# Microcontroller.net
KiCad netlist of a schematic drawn in Altium Designer
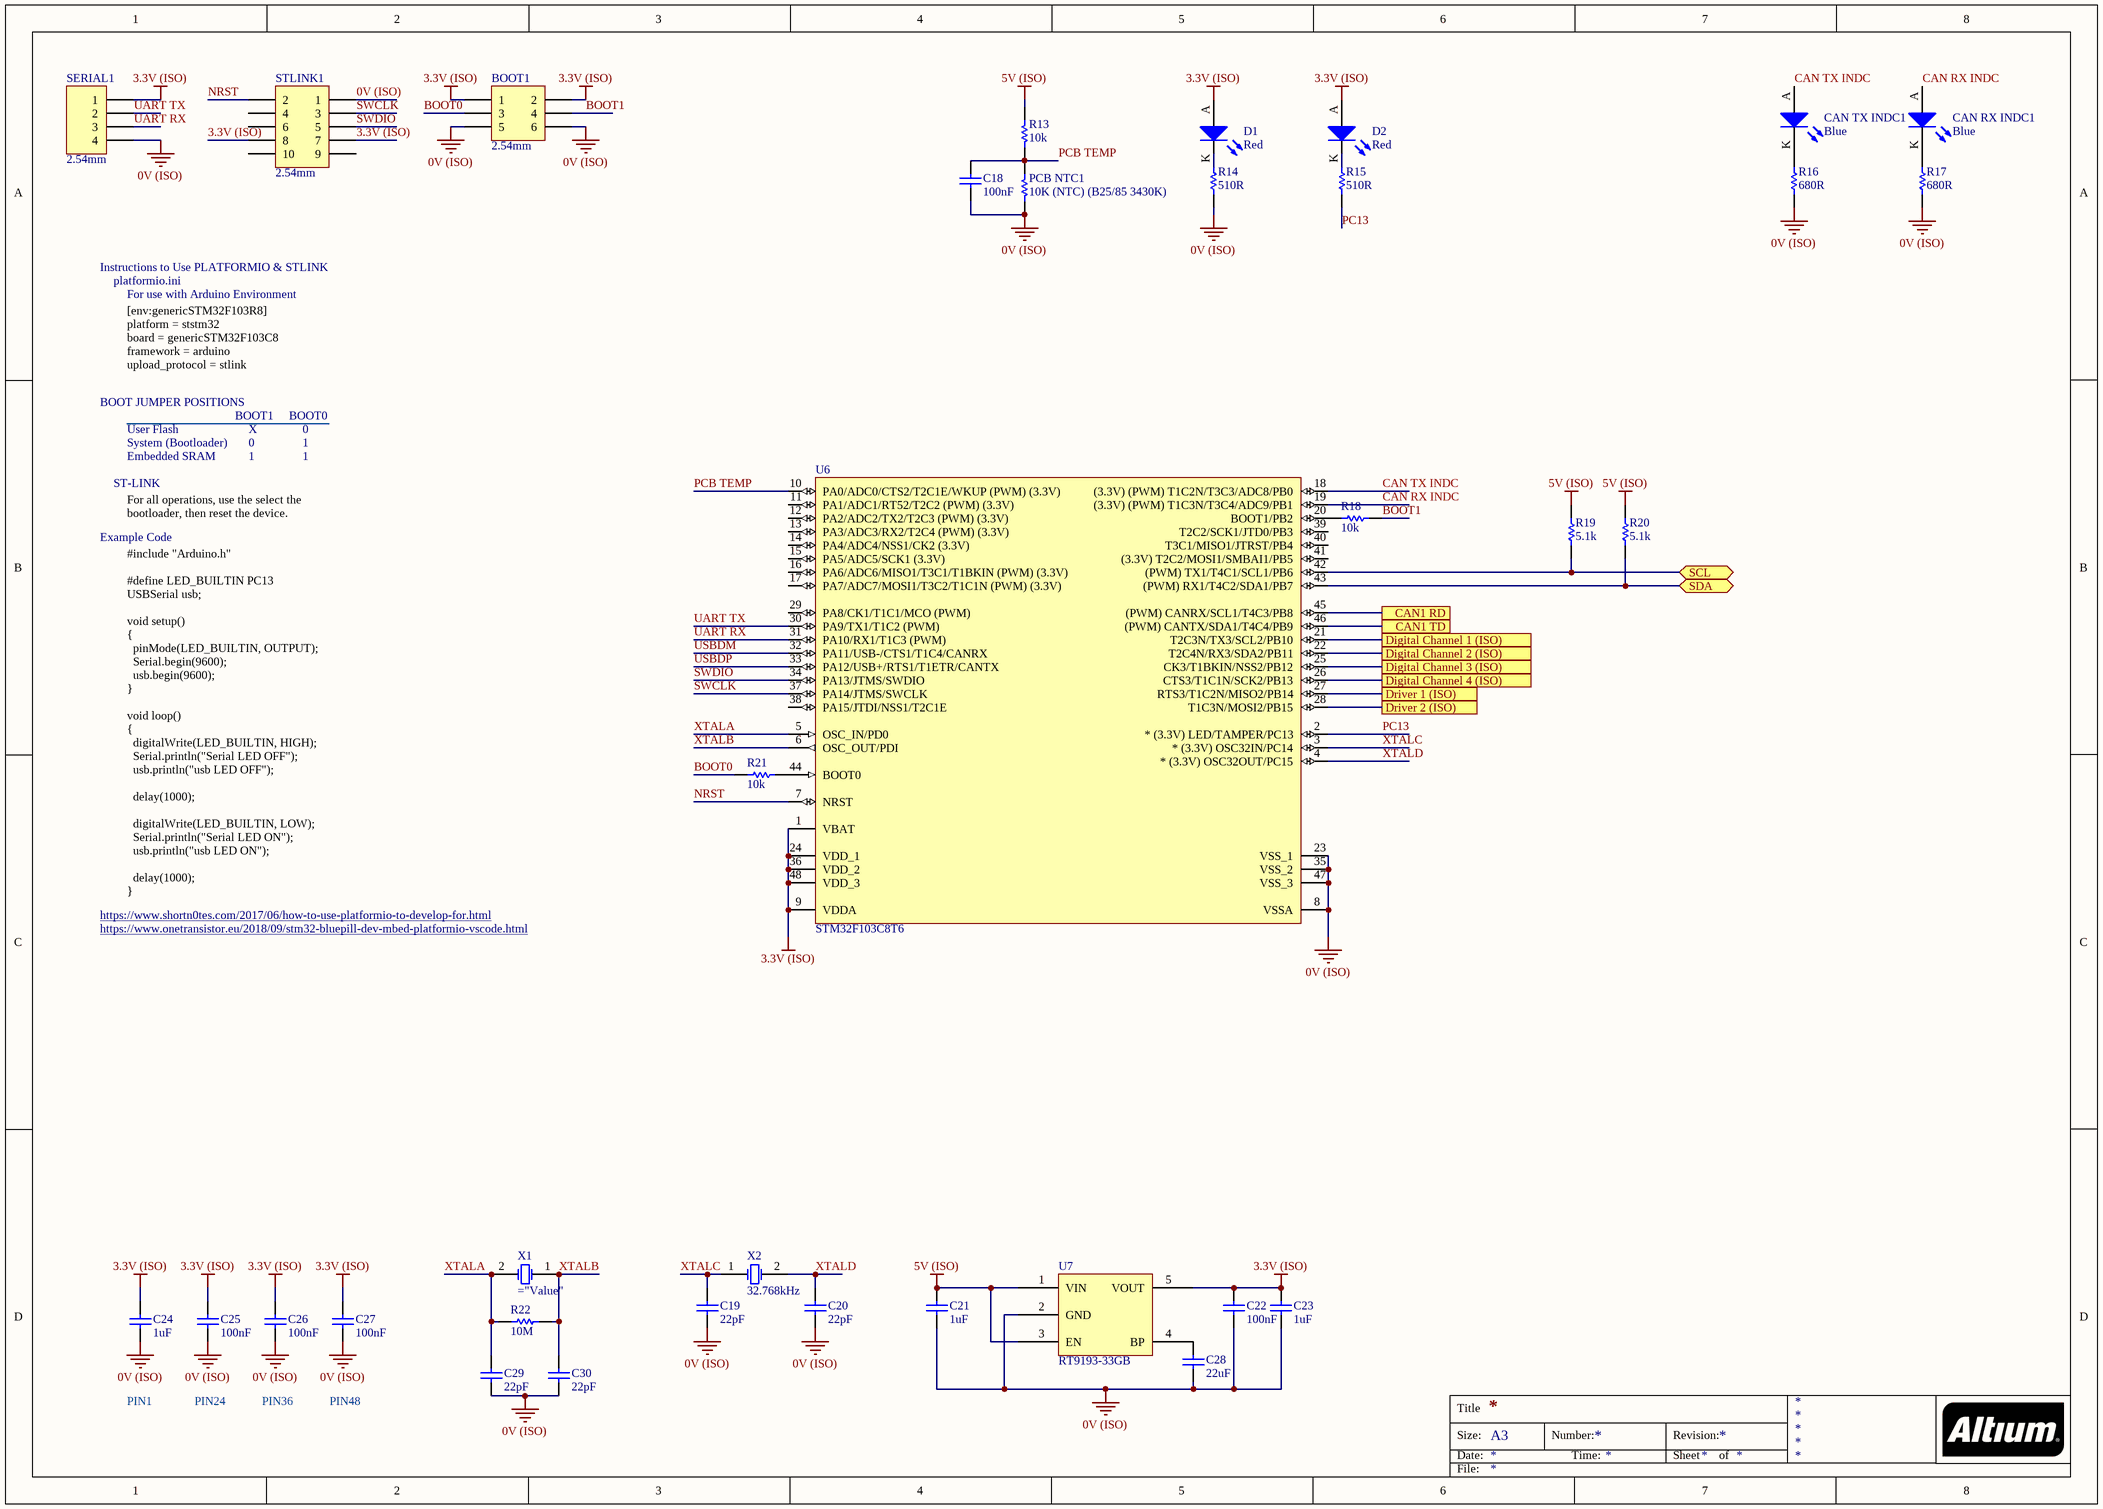
[diagram p0: Microcontroller.SchDoc]

(export (version "E")
  (design (tool "Eeschema 10.0.6"))
  (components
    (comp (ref "BOOT1")
      (value "2.54mm")
      (footprint "TH 2.54mm Header 2x3")
      (fields (field (name "PART NUMBER") "TH 2.54mm Header 2x3") (field (name "CONTACT") "NA"))
      (libsource (lib "ts_20-standard-connectors") (part "Header 2x3"))
    )
    (comp (ref "C18")
      (value "100nF")
      (footprint "0805")
      (fields
        (field (name "PART NUMBER") "GCM21BR71E104KA37L")
        (field (name "TOLERANCE") "10%")
        (field (name "MANUFACTURER") "muRata")
      )
      (libsource (lib "ts_20-standard-library") (part "Capacitor"))
    )
    (comp (ref "C19")
      (value "22pF")
      (footprint "0805")
      (fields
        (field (name "PART NUMBER") "GCM21B5C1H220JA37L")
        (field (name "TOLERANCE") "5%")
        (field (name "MANUFACTURER") "muRata")
      )
      (libsource (lib "ts_20-standard-library") (part "Capacitor"))
    )
    (comp (ref "C20")
      (value "22pF")
      (footprint "0805")
      (fields
        (field (name "PART NUMBER") "GCM21B5C1H220JA37L")
        (field (name "TOLERANCE") "5%")
        (field (name "MANUFACTURER") "muRata")
      )
      (libsource (lib "ts_20-standard-library") (part "Capacitor"))
    )
    (comp (ref "C21")
      (value "1uF")
      (footprint "0805")
      (fields
        (field (name "PART NUMBER") "AC0805KKX7R8BB105")
        (field (name "TOLERANCE") "10%")
        (field (name "MANUFACTURER") "YAGEO")
      )
      (libsource (lib "ts_20-standard-library") (part "Capacitor"))
    )
    (comp (ref "C22")
      (value "100nF")
      (footprint "0805")
      (fields
        (field (name "PART NUMBER") "GCM21BR71E104KA37L")
        (field (name "TOLERANCE") "10%")
        (field (name "MANUFACTURER") "muRata")
      )
      (libsource (lib "ts_20-standard-library") (part "Capacitor"))
    )
    (comp (ref "C23")
      (value "1uF")
      (footprint "0805")
      (fields
        (field (name "PART NUMBER") "AC0805KKX7R8BB105")
        (field (name "TOLERANCE") "10%")
        (field (name "MANUFACTURER") "YAGEO")
      )
      (libsource (lib "ts_20-standard-library") (part "Capacitor"))
    )
    (comp (ref "C24")
      (value "1uF")
      (footprint "0805")
      (fields
        (field (name "PART NUMBER") "AC0805KKX7R8BB105")
        (field (name "TOLERANCE") "10%")
        (field (name "MANUFACTURER") "YAGEO")
      )
      (libsource (lib "ts_20-standard-library") (part "Capacitor"))
    )
    (comp (ref "C25")
      (value "100nF")
      (footprint "0805")
      (fields
        (field (name "PART NUMBER") "GCM21BR71E104KA37L")
        (field (name "TOLERANCE") "10%")
        (field (name "MANUFACTURER") "muRata")
      )
      (libsource (lib "ts_20-standard-library") (part "Capacitor"))
    )
    (comp (ref "C26")
      (value "100nF")
      (footprint "0805")
      (fields
        (field (name "PART NUMBER") "GCM21BR71E104KA37L")
        (field (name "TOLERANCE") "10%")
        (field (name "MANUFACTURER") "muRata")
      )
      (libsource (lib "ts_20-standard-library") (part "Capacitor"))
    )
    (comp (ref "C27")
      (value "100nF")
      (footprint "0805")
      (fields
        (field (name "PART NUMBER") "GCM21BR71E104KA37L")
        (field (name "TOLERANCE") "10%")
        (field (name "MANUFACTURER") "muRata")
      )
      (libsource (lib "ts_20-standard-library") (part "Capacitor"))
    )
    (comp (ref "C28")
      (value "22uF")
      (footprint "0805")
      (fields
        (field (name "PART NUMBER") "GRM21BR61A226ME51L")
        (field (name "TOLERANCE") "20%")
        (field (name "MANUFACTURER") "muRata")
      )
      (libsource (lib "ts_20-standard-library") (part "Capacitor"))
    )
    (comp (ref "C29")
      (value "22pF")
      (footprint "0805")
      (fields
        (field (name "PART NUMBER") "GCM21B5C1H220JA37L")
        (field (name "TOLERANCE") "5%")
        (field (name "MANUFACTURER") "muRata")
      )
      (libsource (lib "ts_20-standard-library") (part "Capacitor"))
    )
    (comp (ref "C30")
      (value "22pF")
      (footprint "0805")
      (fields
        (field (name "PART NUMBER") "GCM21B5C1H220JA37L")
        (field (name "TOLERANCE") "5%")
        (field (name "MANUFACTURER") "muRata")
      )
      (libsource (lib "ts_20-standard-library") (part "Capacitor"))
    )
    (comp (ref "CAN RX INDC1")
      (value "Blue")
      (footprint "0805 LED")
      (description "LED BLUE CLEAR 2012 SMD")
      (fields
        (field (name "PART NUMBER") "SML-MN2BCTT86C")
        (field (name "MANUFACTURER") "ROHM Semiconductor")
      )
      (libsource (lib "ts_20-standard-library") (part "LED"))
    )
    (comp (ref "CAN TX INDC1")
      (value "Blue")
      (footprint "0805 LED")
      (description "LED BLUE CLEAR 2012 SMD")
      (fields
        (field (name "PART NUMBER") "SML-MN2BCTT86C")
        (field (name "MANUFACTURER") "ROHM Semiconductor")
      )
      (libsource (lib "ts_20-standard-library") (part "LED"))
    )
    (comp (ref "D1")
      (value "Red")
      (footprint "0805 LED")
      (description "Red LED Indication - Discrete 1.75V 0805 (2012 Metric)")
      (fields (field (name "MANUFACTURER") "ROHM Semiconductor") (field (name "PART NUMBER") "SML-210LTT86"))
      (libsource (lib "ts_20-standard-library") (part "LED"))
    )
    (comp (ref "D2")
      (value "Red")
      (footprint "0805 LED")
      (description "Red LED Indication - Discrete 1.75V 0805 (2012 Metric)")
      (fields (field (name "MANUFACTURER") "ROHM Semiconductor") (field (name "PART NUMBER") "SML-210LTT86"))
      (libsource (lib "ts_20-standard-library") (part "LED"))
    )
    (comp (ref "PCB NTC1")
      (value "10K (NTC) (B25/85 3430K)")
      (footprint "0805")
      (fields
        (field (name "PART NUMBER") "NTCS0805E3103FLT")
        (field (name "MANUFACTURER") "Vishay Beyschlag")
        (field (name "TOLERANCE") "0.01")
      )
      (libsource (lib "ts_20-standard-library") (part "Resistor"))
    )
    (comp (ref "R13")
      (value "10k")
      (footprint "0805")
      (fields
        (field (name "PART NUMBER") "RC0805FR0710KL")
        (field (name "MANUFACTURER") "YAGEO")
        (field (name "TOLERANCE") "0.01")
      )
      (libsource (lib "ts_20-standard-library") (part "Resistor"))
    )
    (comp (ref "R14")
      (value "510R")
      (footprint "0805")
      (fields
        (field (name "MANUFACTURER") "YAGEO")
        (field (name "PART NUMBER") "RC0805FR07510RL")
        (field (name "TOLERANCE") "0.01")
      )
      (libsource (lib "ts_20-standard-library") (part "Resistor"))
    )
    (comp (ref "R15")
      (value "510R")
      (footprint "0805")
      (fields
        (field (name "MANUFACTURER") "YAGEO")
        (field (name "PART NUMBER") "RC0805FR07510RL")
        (field (name "TOLERANCE") "0.01")
      )
      (libsource (lib "ts_20-standard-library") (part "Resistor"))
    )
    (comp (ref "R16")
      (value "680R")
      (footprint "0805")
      (fields
        (field (name "PART NUMBER") "RC0805FR07680RL")
        (field (name "MANUFACTURER") "YAGEO")
        (field (name "TOLERANCE") "0.01")
      )
      (libsource (lib "ts_20-standard-library") (part "Resistor"))
    )
    (comp (ref "R17")
      (value "680R")
      (footprint "0805")
      (fields
        (field (name "PART NUMBER") "RC0805FR07680RL")
        (field (name "MANUFACTURER") "YAGEO")
        (field (name "TOLERANCE") "0.01")
      )
      (libsource (lib "ts_20-standard-library") (part "Resistor"))
    )
    (comp (ref "R18")
      (value "10k")
      (footprint "0805")
      (fields
        (field (name "PART NUMBER") "RC0805FR0710KL")
        (field (name "MANUFACTURER") "YAGEO")
        (field (name "TOLERANCE") "0.01")
      )
      (libsource (lib "ts_20-standard-library") (part "Resistor"))
    )
    (comp (ref "R19")
      (value "5.1k")
      (footprint "0805")
      (fields
        (field (name "PART NUMBER") "RC0805FR075K1L")
        (field (name "MANUFACTURER") "YAGEO")
        (field (name "TOLERANCE") "0.01")
      )
      (libsource (lib "ts_20-standard-library") (part "Resistor"))
    )
    (comp (ref "R20")
      (value "5.1k")
      (footprint "0805")
      (fields
        (field (name "PART NUMBER") "RC0805FR075K1L")
        (field (name "MANUFACTURER") "YAGEO")
        (field (name "TOLERANCE") "0.01")
      )
      (libsource (lib "ts_20-standard-library") (part "Resistor"))
    )
    (comp (ref "R21")
      (value "10k")
      (footprint "0805")
      (fields
        (field (name "PART NUMBER") "RC0805FR0710KL")
        (field (name "MANUFACTURER") "YAGEO")
        (field (name "TOLERANCE") "0.01")
      )
      (libsource (lib "ts_20-standard-library") (part "Resistor"))
    )
    (comp (ref "R22")
      (value "10M")
      (footprint "0805")
      (fields
        (field (name "PART NUMBER") "RC0805FR0710ML")
        (field (name "MANUFACTURER") "YAGEO")
        (field (name "TOLERANCE") "0.01")
      )
      (libsource (lib "ts_20-standard-library") (part "Resistor"))
    )
    (comp (ref "SERIAL1")
      (value "2.54mm")
      (footprint "TH 2.54mm Header 1x4")
      (fields (field (name "PART NUMBER") "TH 2.54mm Header 1x4") (field (name "CONTACT") "NA"))
      (libsource (lib "ts_20-standard-connectors") (part "Header 1x4"))
    )
    (comp (ref "STLINK1")
      (value "2.54mm")
      (footprint "TH 2.54mm Header 2x5")
      (fields (field (name "PART NUMBER") "TH 2.54mm Header 2x5") (field (name "CONTACT") "NA"))
      (libsource (lib "ts_20-standard-connectors") (part "Header 2x5"))
    )
    (comp (ref "U6")
      (value "STM32F103C8T6")
      (footprint "STM 48-LQFP")
      (description "ARM® Cortex®-M3 STM32F1 Microcontroller IC 32-Bit 72MHz 64KB (64K x 8) FLASH")
      (fields
        (field (name "MANUFACTURER") "STMicroelectronics")
        (field (name "DIGIKEY PART NUMBER") "497-6063-ND")
      )
      (libsource (lib "ts_20-standard-library") (part "STM32F103C8T6"))
    )
    (comp (ref "U7")
      (value "RT9193-33GB")
      (footprint "RICHTEK SOT-23-5")
      (description "IC REG LINEAR 3.3V 300MA SOT23-5")
      (fields (field (name "MANUFACTURER") "Richtek") (field (name "DIGIKEY PART NUMBER") "1028-1014-1-ND"))
      (libsource (lib "ts_20-standard-library") (part "RT9193-33GB"))
    )
    (comp (ref "X1")
      (value "~")
      (footprint "Abracon HC-49/US")
      (fields
        (field (name "PART NUMBER") "ABLS-16.000MHZ-B4-T")
        (field (name "MANUFACTURER") "Abracon LLC")
        (field (name "DIGIKEY PART NUMBER") "535-10226-1-ND")
      )
      (libsource (lib "ts_20-standard-library") (part "Crystal"))
    )
    (comp (ref "X2")
      (value "32.768kHz")
      (footprint "EPSON 2-SMD")
      (fields
        (field (name "PART NUMBER") "FC-135 32.7680KA-A5")
        (field (name "MANUFACTURER") "EPSON")
        (field (name "DIGIKEY PART NUMBER") "SER4103TR-ND")
      )
      (libsource (lib "ts_20-standard-library") (part "Crystal"))
    )
  )
  (nets
    (net (code "1") (name "/BOOT0") (class "Default")
      (node (ref "BOOT1") (pin "3") (pinfunction "3_3") (pintype "passive"))
      (node (ref "R21") (pin "1") (pinfunction "1_1") (pintype "passive"))
    )
    (net (code "2") (name "/BOOT1") (class "Default")
      (node (ref "BOOT1") (pin "4") (pinfunction "4_4") (pintype "passive"))
      (node (ref "R18") (pin "2") (pinfunction "2_2") (pintype "passive"))
    )
    (net (code "3") (name "/CAN RX INDC") (class "Default")
      (node (ref "CAN RX INDC1") (pin "A") (pinfunction "A_A") (pintype "passive"))
      (node (ref "U6") (pin "19") (pinfunction "(3.3V)_(PWM)_T1C3N/T3C4/ADC9/PB1_19") (pintype "bidirectional"))
    )
    (net (code "4") (name "/CAN TX INDC") (class "Default")
      (node (ref "CAN TX INDC1") (pin "A") (pinfunction "A_A") (pintype "passive"))
      (node (ref "U6") (pin "18") (pinfunction "(3.3V)_(PWM)_T1C2N/T3C3/ADC8/PB0_18") (pintype "bidirectional"))
    )
    (net (code "5") (name "/CAN1 RD") (class "Default")
      (node (ref "U6") (pin "45") (pinfunction "(PWM)_CANRX/SCL1/T4C3/PB8_45") (pintype "bidirectional"))
    )
    (net (code "6") (name "/CAN1 TD") (class "Default")
      (node (ref "U6") (pin "46") (pinfunction "(PWM)_CANTX/SDA1/T4C4/PB9_46") (pintype "bidirectional"))
    )
    (net (code "7") (name "/Digital Channel 1 (ISO)") (class "Default")
      (node (ref "U6") (pin "21") (pinfunction "T2C3N/TX3/SCL2/PB10_21") (pintype "bidirectional"))
    )
    (net (code "8") (name "/Digital Channel 2 (ISO)") (class "Default")
      (node (ref "U6") (pin "22") (pinfunction "T2C4N/RX3/SDA2/PB11_22") (pintype "bidirectional"))
    )
    (net (code "9") (name "/Digital Channel 3 (ISO)") (class "Default")
      (node (ref "U6") (pin "25") (pinfunction "CK3/T1BKIN/NSS2/PB12_25") (pintype "bidirectional"))
    )
    (net (code "10") (name "/Digital Channel 4 (ISO)") (class "Default")
      (node (ref "U6") (pin "26") (pinfunction "CTS3/T1C1N/SCK2/PB13_26") (pintype "bidirectional"))
    )
    (net (code "11") (name "/Driver 1 (ISO)") (class "Default")
      (node (ref "U6") (pin "27") (pinfunction "RTS3/T1C2N/MISO2/PB14_27") (pintype "bidirectional"))
    )
    (net (code "12") (name "/Driver 2 (ISO)") (class "Default")
      (node (ref "U6") (pin "28") (pinfunction "T1C3N/MOSI2/PB15_28") (pintype "bidirectional"))
    )
    (net (code "13") (name "/NRST") (class "Default")
      (node (ref "STLINK1") (pin "2") (pinfunction "2_2") (pintype "passive"))
      (node (ref "U6") (pin "7") (pinfunction "NRST_7") (pintype "bidirectional"))
    )
    (net (code "14") (name "/PC13") (class "Default")
      (node (ref "R15") (pin "1") (pinfunction "1_1") (pintype "passive"))
      (node (ref "U6") (pin "2") (pinfunction "*_(3.3V)_LED/TAMPER/PC13_2") (pintype "bidirectional"))
    )
    (net (code "15") (name "/PCB TEMP") (class "Default")
      (node (ref "C18") (pin "2") (pinfunction "2_2") (pintype "passive"))
      (node (ref "PCB NTC1") (pin "2") (pinfunction "2_2") (pintype "passive"))
      (node (ref "R13") (pin "1") (pinfunction "1_1") (pintype "passive"))
      (node (ref "U6") (pin "10") (pinfunction "PA0/ADC0/CTS2/T2C1E/WKUP_(PWM)_(3.3V)_10") (pintype "bidirectional"))
    )
    (net (code "16") (name "/SCL") (class "Default")
      (node (ref "R19") (pin "1") (pinfunction "1_1") (pintype "passive"))
      (node (ref "U6") (pin "42") (pinfunction "(PWM)_TX1/T4C1/SCL1/PB6_42") (pintype "bidirectional"))
    )
    (net (code "17") (name "/SDA") (class "Default")
      (node (ref "R20") (pin "1") (pinfunction "1_1") (pintype "passive"))
      (node (ref "U6") (pin "43") (pinfunction "(PWM)_RX1/T4C2/SDA1/PB7_43") (pintype "bidirectional"))
    )
    (net (code "18") (name "/SWCLK") (class "Default")
      (node (ref "STLINK1") (pin "3") (pinfunction "3_3") (pintype "passive"))
      (node (ref "U6") (pin "37") (pinfunction "PA14/JTMS/SWCLK_37") (pintype "bidirectional"))
    )
    (net (code "19") (name "/SWDIO") (class "Default")
      (node (ref "STLINK1") (pin "5") (pinfunction "5_5") (pintype "passive"))
      (node (ref "U6") (pin "34") (pinfunction "PA13/JTMS/SWDIO_34") (pintype "bidirectional"))
    )
    (net (code "20") (name "/UART RX") (class "Default")
      (node (ref "SERIAL1") (pin "3") (pinfunction "3_3") (pintype "passive"))
      (node (ref "U6") (pin "31") (pinfunction "PA10/RX1/T1C3_(PWM)_31") (pintype "bidirectional"))
    )
    (net (code "21") (name "/UART TX") (class "Default")
      (node (ref "SERIAL1") (pin "2") (pinfunction "2_2") (pintype "passive"))
      (node (ref "U6") (pin "30") (pinfunction "PA9/TX1/T1C2_(PWM)_30") (pintype "bidirectional"))
    )
    (net (code "22") (name "/USBDM") (class "Default")
      (node (ref "U6") (pin "32") (pinfunction "PA11/USB-/CTS1/T1C4/CANRX_32") (pintype "bidirectional"))
    )
    (net (code "23") (name "/USBDP") (class "Default")
      (node (ref "U6") (pin "33") (pinfunction "PA12/USB+/RTS1/T1ETR/CANTX_33") (pintype "bidirectional"))
    )
    (net (code "24") (name "/XTALA") (class "Default")
      (node (ref "C29") (pin "2") (pinfunction "2_2") (pintype "passive"))
      (node (ref "R22") (pin "2") (pinfunction "2_2") (pintype "passive"))
      (node (ref "U6") (pin "5") (pinfunction "OSC_IN/PD0_5") (pintype "input"))
      (node (ref "X1") (pin "2") (pinfunction "OSC2_2") (pintype "passive"))
    )
    (net (code "25") (name "/XTALB") (class "Default")
      (node (ref "C30") (pin "2") (pinfunction "2_2") (pintype "passive"))
      (node (ref "R22") (pin "1") (pinfunction "1_1") (pintype "passive"))
      (node (ref "U6") (pin "6") (pinfunction "OSC_OUT/PDI_6") (pintype "output"))
      (node (ref "X1") (pin "1") (pinfunction "OSC1_1") (pintype "passive"))
    )
    (net (code "26") (name "/XTALC") (class "Default")
      (node (ref "C19") (pin "2") (pinfunction "2_2") (pintype "passive"))
      (node (ref "U6") (pin "3") (pinfunction "*_(3.3V)_OSC32IN/PC14_3") (pintype "bidirectional"))
      (node (ref "X2") (pin "1") (pinfunction "OSC1_1") (pintype "passive"))
    )
    (net (code "27") (name "/XTALD") (class "Default")
      (node (ref "C20") (pin "2") (pinfunction "2_2") (pintype "passive"))
      (node (ref "U6") (pin "4") (pinfunction "*_(3.3V)_OSC32OUT/PC15_4") (pintype "bidirectional"))
      (node (ref "X2") (pin "2") (pinfunction "OSC2_2") (pintype "passive"))
    )
    (net (code "28") (name "0V (ISO)") (class "Default")
      (node (ref "BOOT1") (pin "5") (pinfunction "5_5") (pintype "passive"))
      (node (ref "BOOT1") (pin "6") (pinfunction "6_6") (pintype "passive"))
      (node (ref "C18") (pin "1") (pinfunction "1_1") (pintype "passive"))
      (node (ref "C19") (pin "1") (pinfunction "1_1") (pintype "passive"))
      (node (ref "C20") (pin "1") (pinfunction "1_1") (pintype "passive"))
      (node (ref "C21") (pin "1") (pinfunction "1_1") (pintype "passive"))
      (node (ref "C22") (pin "1") (pinfunction "1_1") (pintype "passive"))
      (node (ref "C23") (pin "1") (pinfunction "1_1") (pintype "passive"))
      (node (ref "C24") (pin "1") (pinfunction "1_1") (pintype "passive"))
      (node (ref "C25") (pin "1") (pinfunction "1_1") (pintype "passive"))
      (node (ref "C26") (pin "1") (pinfunction "1_1") (pintype "passive"))
      (node (ref "C27") (pin "1") (pinfunction "1_1") (pintype "passive"))
      (node (ref "C28") (pin "1") (pinfunction "1_1") (pintype "passive"))
      (node (ref "C29") (pin "1") (pinfunction "1_1") (pintype "passive"))
      (node (ref "C30") (pin "1") (pinfunction "1_1") (pintype "passive"))
      (node (ref "PCB NTC1") (pin "1") (pinfunction "1_1") (pintype "passive"))
      (node (ref "R14") (pin "1") (pinfunction "1_1") (pintype "passive"))
      (node (ref "R16") (pin "1") (pinfunction "1_1") (pintype "passive"))
      (node (ref "R17") (pin "1") (pinfunction "1_1") (pintype "passive"))
      (node (ref "SERIAL1") (pin "4") (pinfunction "4_4") (pintype "passive"))
      (node (ref "STLINK1") (pin "1") (pinfunction "1_1") (pintype "passive"))
      (node (ref "U6") (pin "23") (pinfunction "VSS_1_23") (pintype "power_in"))
      (node (ref "U6") (pin "35") (pinfunction "VSS_2_35") (pintype "power_in"))
      (node (ref "U6") (pin "47") (pinfunction "VSS_3_47") (pintype "power_in"))
      (node (ref "U6") (pin "8") (pinfunction "VSSA_8") (pintype "power_in"))
      (node (ref "U7") (pin "2") (pinfunction "GND_2") (pintype "passive"))
    )
    (net (code "29") (name "3.3V (ISO)") (class "Default")
      (node (ref "BOOT1") (pin "1") (pinfunction "1_1") (pintype "passive"))
      (node (ref "BOOT1") (pin "2") (pinfunction "2_2") (pintype "passive"))
      (node (ref "C22") (pin "2") (pinfunction "2_2") (pintype "passive"))
      (node (ref "C23") (pin "2") (pinfunction "2_2") (pintype "passive"))
      (node (ref "C24") (pin "2") (pinfunction "2_2") (pintype "passive"))
      (node (ref "C25") (pin "2") (pinfunction "2_2") (pintype "passive"))
      (node (ref "C26") (pin "2") (pinfunction "2_2") (pintype "passive"))
      (node (ref "C27") (pin "2") (pinfunction "2_2") (pintype "passive"))
      (node (ref "D1") (pin "A") (pinfunction "A_A") (pintype "passive"))
      (node (ref "D2") (pin "A") (pinfunction "A_A") (pintype "passive"))
      (node (ref "SERIAL1") (pin "1") (pinfunction "1_1") (pintype "passive"))
      (node (ref "STLINK1") (pin "7") (pinfunction "7_7") (pintype "passive"))
      (node (ref "STLINK1") (pin "8") (pinfunction "8_8") (pintype "passive"))
      (node (ref "U6") (pin "1") (pinfunction "VBAT_1") (pintype "power_in"))
      (node (ref "U6") (pin "24") (pinfunction "VDD_1_24") (pintype "power_in"))
      (node (ref "U6") (pin "36") (pinfunction "VDD_2_36") (pintype "power_in"))
      (node (ref "U6") (pin "48") (pinfunction "VDD_3_48") (pintype "power_in"))
      (node (ref "U6") (pin "9") (pinfunction "VDDA_9") (pintype "power_in"))
      (node (ref "U7") (pin "5") (pinfunction "VOUT_5") (pintype "passive"))
    )
    (net (code "30") (name "5V (ISO)") (class "Default")
      (node (ref "C21") (pin "2") (pinfunction "2_2") (pintype "passive"))
      (node (ref "R13") (pin "2") (pinfunction "2_2") (pintype "passive"))
      (node (ref "R19") (pin "2") (pinfunction "2_2") (pintype "passive"))
      (node (ref "R20") (pin "2") (pinfunction "2_2") (pintype "passive"))
      (node (ref "U7") (pin "1") (pinfunction "VIN_1") (pintype "passive"))
      (node (ref "U7") (pin "3") (pinfunction "EN_3") (pintype "passive"))
    )
    (net (code "31") (name "Net-(CAN RX INDC1-PadK)") (class "Default")
      (node (ref "CAN RX INDC1") (pin "K") (pinfunction "K_K") (pintype "passive"))
      (node (ref "R17") (pin "2") (pinfunction "2_2") (pintype "passive"))
    )
    (net (code "32") (name "Net-(CAN TX INDC1-PadK)") (class "Default")
      (node (ref "CAN TX INDC1") (pin "K") (pinfunction "K_K") (pintype "passive"))
      (node (ref "R16") (pin "2") (pinfunction "2_2") (pintype "passive"))
    )
    (net (code "33") (name "Net-(D1-PadK)") (class "Default")
      (node (ref "D1") (pin "K") (pinfunction "K_K") (pintype "passive"))
      (node (ref "R14") (pin "2") (pinfunction "2_2") (pintype "passive"))
    )
    (net (code "34") (name "Net-(D2-PadK)") (class "Default")
      (node (ref "D2") (pin "K") (pinfunction "K_K") (pintype "passive"))
      (node (ref "R15") (pin "2") (pinfunction "2_2") (pintype "passive"))
    )
    (net (code "35") (name "Net-(U6-BOOT0)") (class "Default")
      (node (ref "R21") (pin "2") (pinfunction "2_2") (pintype "passive"))
      (node (ref "U6") (pin "44") (pinfunction "BOOT0_44") (pintype "input"))
    )
    (net (code "36") (name "Net-(U6-BOOT1{slash}PB2)") (class "Default")
      (node (ref "R18") (pin "1") (pinfunction "1_1") (pintype "passive"))
      (node (ref "U6") (pin "20") (pinfunction "BOOT1/PB2_20") (pintype "bidirectional"))
    )
    (net (code "37") (name "Net-(U7-BP)") (class "Default")
      (node (ref "C28") (pin "2") (pinfunction "2_2") (pintype "passive"))
      (node (ref "U7") (pin "4") (pinfunction "BP_4") (pintype "passive"))
    )
    (net (code "38") (name "unconnected-(STLINK1-Pad4)") (class "Default")
      (node (ref "STLINK1") (pin "4") (pinfunction "4_4") (pintype "passive"))
    )
    (net (code "39") (name "unconnected-(STLINK1-Pad6)") (class "Default")
      (node (ref "STLINK1") (pin "6") (pinfunction "6_6") (pintype "passive"))
    )
    (net (code "40") (name "unconnected-(STLINK1-Pad9)") (class "Default")
      (node (ref "STLINK1") (pin "9") (pinfunction "9_9") (pintype "passive"))
    )
    (net (code "41") (name "unconnected-(STLINK1-Pad10)") (class "Default")
      (node (ref "STLINK1") (pin "10") (pinfunction "10_10") (pintype "passive"))
    )
    (net (code "42") (name "unconnected-(U6-(3.3V)_T2C2{slash}MOSI1{slash}SMBAI1{slash}PB5-Pad41)") (class "Default")
      (node (ref "U6") (pin "41") (pinfunction "(3.3V)_T2C2/MOSI1/SMBAI1/PB5_41") (pintype "bidirectional"))
    )
    (net (code "43") (name "unconnected-(U6-PA1{slash}ADC1{slash}RT52{slash}T2C2_(PWM)_(3.3V)-Pad11)") (class "Default")
      (node (ref "U6") (pin "11") (pinfunction "PA1/ADC1/RT52/T2C2_(PWM)_(3.3V)_11") (pintype "bidirectional"))
    )
    (net (code "44") (name "unconnected-(U6-PA2{slash}ADC2{slash}TX2{slash}T2C3_(PWM)_(3.3V)-Pad12)") (class "Default")
      (node (ref "U6") (pin "12") (pinfunction "PA2/ADC2/TX2/T2C3_(PWM)_(3.3V)_12") (pintype "bidirectional"))
    )
    (net (code "45") (name "unconnected-(U6-PA3{slash}ADC3{slash}RX2{slash}T2C4_(PWM)_(3.3V)-Pad13)") (class "Default")
      (node (ref "U6") (pin "13") (pinfunction "PA3/ADC3/RX2/T2C4_(PWM)_(3.3V)_13") (pintype "bidirectional"))
    )
    (net (code "46") (name "unconnected-(U6-PA4{slash}ADC4{slash}NSS1{slash}CK2_(3.3V)-Pad14)") (class "Default")
      (node (ref "U6") (pin "14") (pinfunction "PA4/ADC4/NSS1/CK2_(3.3V)_14") (pintype "bidirectional"))
    )
    (net (code "47") (name "unconnected-(U6-PA5{slash}ADC5{slash}SCK1_(3.3V)-Pad15)") (class "Default")
      (node (ref "U6") (pin "15") (pinfunction "PA5/ADC5/SCK1_(3.3V)_15") (pintype "bidirectional"))
    )
    (net (code "48") (name "unconnected-(U6-PA6{slash}ADC6{slash}MISO1{slash}T3C1{slash}T1BKIN_(PWM)_(3.3V)-Pad16)") (class "Default")
      (node (ref "U6") (pin "16") (pinfunction "PA6/ADC6/MISO1/T3C1/T1BKIN_(PWM)_(3.3V)_16") (pintype "bidirectional"))
    )
    (net (code "49") (name "unconnected-(U6-PA7{slash}ADC7{slash}MOSI1{slash}T3C2{slash}T1C1N_(PWM)_(3.3V)-Pad17)") (class "Default")
      (node (ref "U6") (pin "17") (pinfunction "PA7/ADC7/MOSI1/T3C2/T1C1N_(PWM)_(3.3V)_17") (pintype "bidirectional"))
    )
    (net (code "50") (name "unconnected-(U6-PA8{slash}CK1{slash}T1C1{slash}MCO_(PWM)-Pad29)") (class "Default")
      (node (ref "U6") (pin "29") (pinfunction "PA8/CK1/T1C1/MCO_(PWM)_29") (pintype "bidirectional"))
    )
    (net (code "51") (name "unconnected-(U6-PA15{slash}JTDI{slash}NSS1{slash}T2C1E-Pad38)") (class "Default")
      (node (ref "U6") (pin "38") (pinfunction "PA15/JTDI/NSS1/T2C1E_38") (pintype "bidirectional"))
    )
    (net (code "52") (name "unconnected-(U6-T2C2{slash}SCK1{slash}JTD0{slash}PB3-Pad39)") (class "Default")
      (node (ref "U6") (pin "39") (pinfunction "T2C2/SCK1/JTD0/PB3_39") (pintype "bidirectional"))
    )
    (net (code "53") (name "unconnected-(U6-T3C1{slash}MISO1{slash}JTRST{slash}PB4-Pad40)") (class "Default")
      (node (ref "U6") (pin "40") (pinfunction "T3C1/MISO1/JTRST/PB4_40") (pintype "bidirectional"))
    )
  )
)
